# BSD_Final_Design.net
KiCad netlist of a schematic drawn in EAGLE
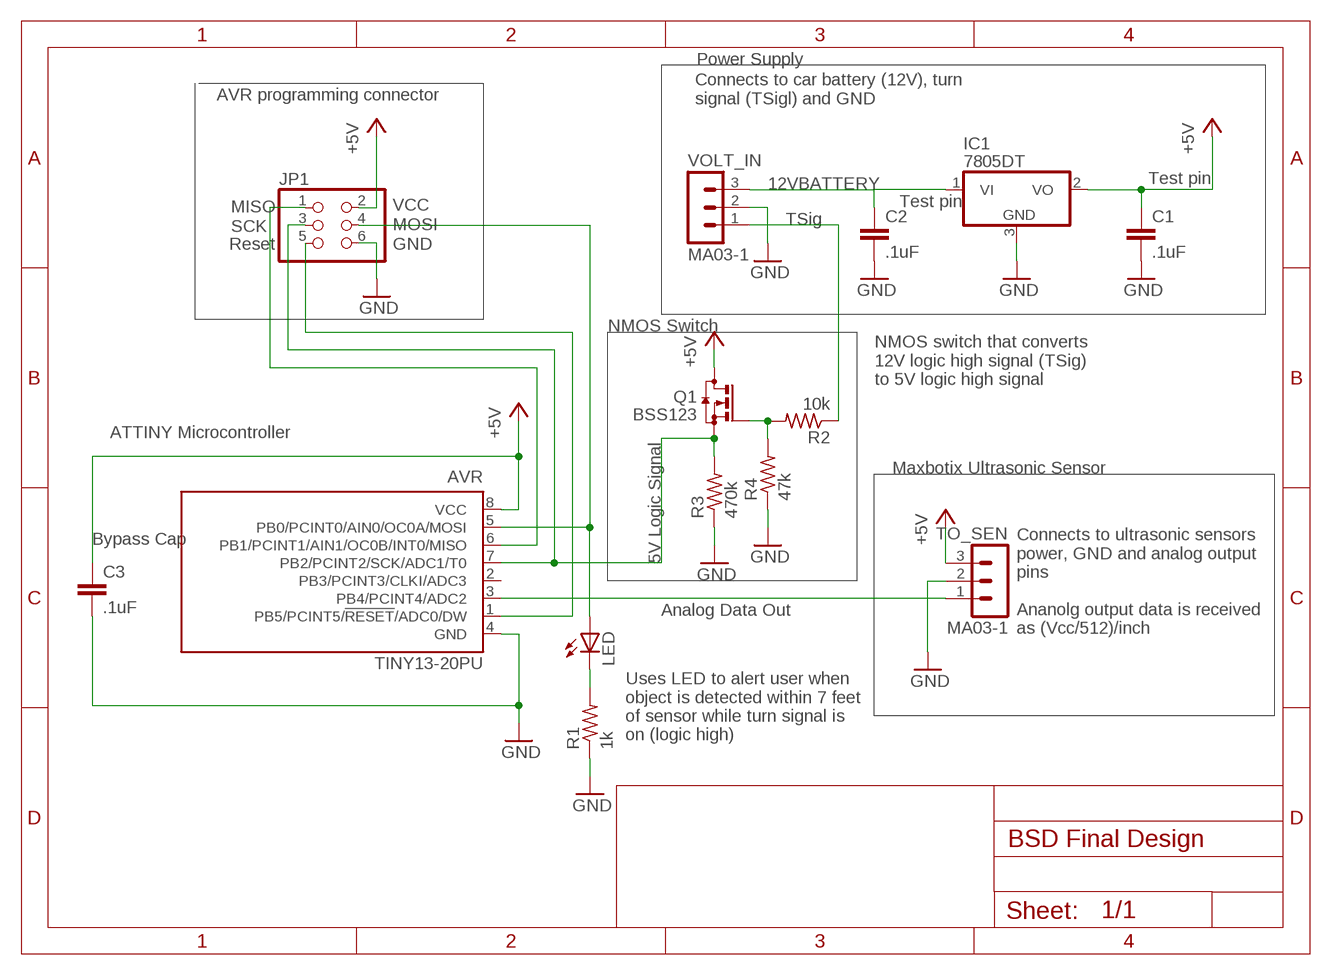
[diagram p0: schematic, sheet 1]

(export (version "E")
  (design (tool "Eeschema 10.0.6"))
  (components
    (comp (ref "AVR")
      (value "TINY13-20PU")
      (footprint "eagle-import:DIL08")
      (fields (field (name "MPN") "ATTINY13-20PU"))
      (libsource (lib "eagle-import") (part "TINY13PU-20"))
    )
    (comp (ref "C1")
      (value ".1uF")
      (footprint "eagle-import:C0805")
      (libsource (lib "eagle-import") (part "C-EUC0805"))
    )
    (comp (ref "C2")
      (value ".1uF")
      (footprint "eagle-import:C0805")
      (libsource (lib "eagle-import") (part "C-EUC0805"))
    )
    (comp (ref "C3")
      (value ".1uF")
      (footprint "eagle-import:C0805")
      (libsource (lib "eagle-import") (part "C-EUC0805"))
    )
    (comp (ref "IC1")
      (value "7805DT")
      (footprint "eagle-import:TO252")
      (libsource (lib "eagle-import") (part "78DT05"))
    )
    (comp (ref "JP1")
      (value "PINHD-2X3")
      (footprint "eagle-import:2X03")
      (libsource (lib "eagle-import") (part "PINHD-2X3"))
    )
    (comp (ref "LED")
      (value "LED5MM")
      (footprint "eagle-import:LED5MM")
      (libsource (lib "eagle-import") (part "LED5MM"))
    )
    (comp (ref "Q1")
      (value "BSS123")
      (footprint "eagle-import:SOT23")
      (libsource (lib "eagle-import") (part "BSS123"))
    )
    (comp (ref "R1")
      (value "1k")
      (footprint "eagle-import:R0805")
      (libsource (lib "eagle-import") (part "R-US_R0805"))
    )
    (comp (ref "R2")
      (value "10k")
      (footprint "eagle-import:R0805")
      (libsource (lib "eagle-import") (part "R-US_R0805"))
    )
    (comp (ref "R3")
      (value "470k")
      (footprint "eagle-import:R0805")
      (libsource (lib "eagle-import") (part "R-US_R0805"))
    )
    (comp (ref "R4")
      (value "47k")
      (footprint "eagle-import:R0805")
      (libsource (lib "eagle-import") (part "R-US_R0805"))
    )
    (comp (ref "TO_SEN")
      (value "MA03-1")
      (footprint "eagle-import:MA03-1")
      (libsource (lib "eagle-import") (part "MA03-1"))
    )
    (comp (ref "VOLT_IN")
      (value "MA03-1")
      (footprint "eagle-import:MA03-1")
      (libsource (lib "eagle-import") (part "MA03-1"))
    )
  )
  (nets
    (net (code "1") (name "+5V") (class "Default")
      (node (ref "AVR") (pin "8") (pinfunction "VCC_8") (pintype "power_in"))
      (node (ref "C1") (pin "1") (pinfunction "1_1") (pintype "passive"))
      (node (ref "C3") (pin "1") (pinfunction "1_1") (pintype "passive"))
      (node (ref "IC1") (pin "2") (pinfunction "VO_2") (pintype "passive"))
      (node (ref "JP1") (pin "2") (pinfunction "2_2") (pintype "passive"))
      (node (ref "Q1") (pin "3") (pinfunction "D_3") (pintype "passive"))
      (node (ref "TO_SEN") (pin "3") (pinfunction "3_3") (pintype "passive"))
    )
    (net (code "2") (name "/12VBATTERY") (class "Default")
      (node (ref "C2") (pin "1") (pinfunction "1_1") (pintype "passive"))
      (node (ref "IC1") (pin "1") (pinfunction "VI_1") (pintype "input"))
      (node (ref "VOLT_IN") (pin "3") (pinfunction "3_3") (pintype "passive"))
    )
    (net (code "3") (name "GND") (class "Default")
      (node (ref "AVR") (pin "4") (pinfunction "GND_4") (pintype "power_in"))
      (node (ref "C1") (pin "2") (pinfunction "2_2") (pintype "passive"))
      (node (ref "C2") (pin "2") (pinfunction "2_2") (pintype "passive"))
      (node (ref "C3") (pin "2") (pinfunction "2_2") (pintype "passive"))
      (node (ref "IC1") (pin "3") (pinfunction "GND_3") (pintype "passive"))
      (node (ref "JP1") (pin "6") (pinfunction "6_6") (pintype "passive"))
      (node (ref "R1") (pin "1") (pinfunction "1_1") (pintype "passive"))
      (node (ref "R3") (pin "1") (pinfunction "1_1") (pintype "passive"))
      (node (ref "R4") (pin "1") (pinfunction "1_1") (pintype "passive"))
      (node (ref "TO_SEN") (pin "2") (pinfunction "2_2") (pintype "passive"))
      (node (ref "VOLT_IN") (pin "2") (pinfunction "2_2") (pintype "passive"))
    )
    (net (code "4") (name "Net-(AVR-PB0{slash}PCINT0{slash}AIN0{slash}OC0A{slash}MOSI)") (class "Default")
      (node (ref "AVR") (pin "5") (pinfunction "PB0/PCINT0/AIN0/OC0A/MOSI_5") (pintype "bidirectional"))
      (node (ref "JP1") (pin "4") (pinfunction "4_4") (pintype "passive"))
      (node (ref "LED") (pin "A") (pinfunction "A_A") (pintype "passive"))
    )
    (net (code "5") (name "Net-(AVR-PB1{slash}PCINT1{slash}AIN1{slash}OC0B{slash}INT0{slash}MISO)") (class "Default")
      (node (ref "AVR") (pin "6") (pinfunction "PB1/PCINT1/AIN1/OC0B/INT0/MISO_6") (pintype "bidirectional"))
      (node (ref "JP1") (pin "1") (pinfunction "1_1") (pintype "passive"))
    )
    (net (code "6") (name "Net-(AVR-PB2{slash}PCINT2{slash}SCK{slash}ADC1{slash}T0)") (class "Default")
      (node (ref "AVR") (pin "7") (pinfunction "PB2/PCINT2/SCK/ADC1/T0_7") (pintype "bidirectional"))
      (node (ref "JP1") (pin "3") (pinfunction "3_3") (pintype "passive"))
      (node (ref "Q1") (pin "2") (pinfunction "S_2") (pintype "passive"))
      (node (ref "R3") (pin "2") (pinfunction "2_2") (pintype "passive"))
    )
    (net (code "7") (name "Net-(AVR-PB4{slash}PCINT4{slash}ADC2)") (class "Default")
      (node (ref "AVR") (pin "3") (pinfunction "PB4/PCINT4/ADC2_3") (pintype "bidirectional"))
      (node (ref "TO_SEN") (pin "1") (pinfunction "1_1") (pintype "passive"))
    )
    (net (code "8") (name "Net-(AVR-PB5{slash}PCINT5{slash}~{RESET}{slash}ADC0{slash}DW)") (class "Default")
      (node (ref "AVR") (pin "1") (pinfunction "PB5/PCINT5/~{RESET}/ADC0/DW_1") (pintype "bidirectional"))
      (node (ref "JP1") (pin "5") (pinfunction "5_5") (pintype "passive"))
    )
    (net (code "9") (name "Net-(LED-C)") (class "Default")
      (node (ref "LED") (pin "K") (pinfunction "C_K") (pintype "passive"))
      (node (ref "R1") (pin "2") (pinfunction "2_2") (pintype "passive"))
    )
    (net (code "10") (name "Net-(Q1-G)") (class "Default")
      (node (ref "Q1") (pin "1") (pinfunction "G_1") (pintype "passive"))
      (node (ref "R2") (pin "2") (pinfunction "2_2") (pintype "passive"))
      (node (ref "R4") (pin "2") (pinfunction "2_2") (pintype "passive"))
    )
    (net (code "11") (name "Net-(R2-Pad1)") (class "Default")
      (node (ref "R2") (pin "1") (pinfunction "1_1") (pintype "passive"))
      (node (ref "VOLT_IN") (pin "1") (pinfunction "1_1") (pintype "passive"))
    )
    (net (code "12") (name "unconnected-(AVR-PB3{slash}PCINT3{slash}CLKI{slash}ADC3-Pad2)") (class "Default")
      (node (ref "AVR") (pin "2") (pinfunction "PB3/PCINT3/CLKI/ADC3_2") (pintype "bidirectional"))
    )
  )
)
